# orangepi-util-40pin.net
KiCad netlist of a schematic drawn in EasyEDA Pro
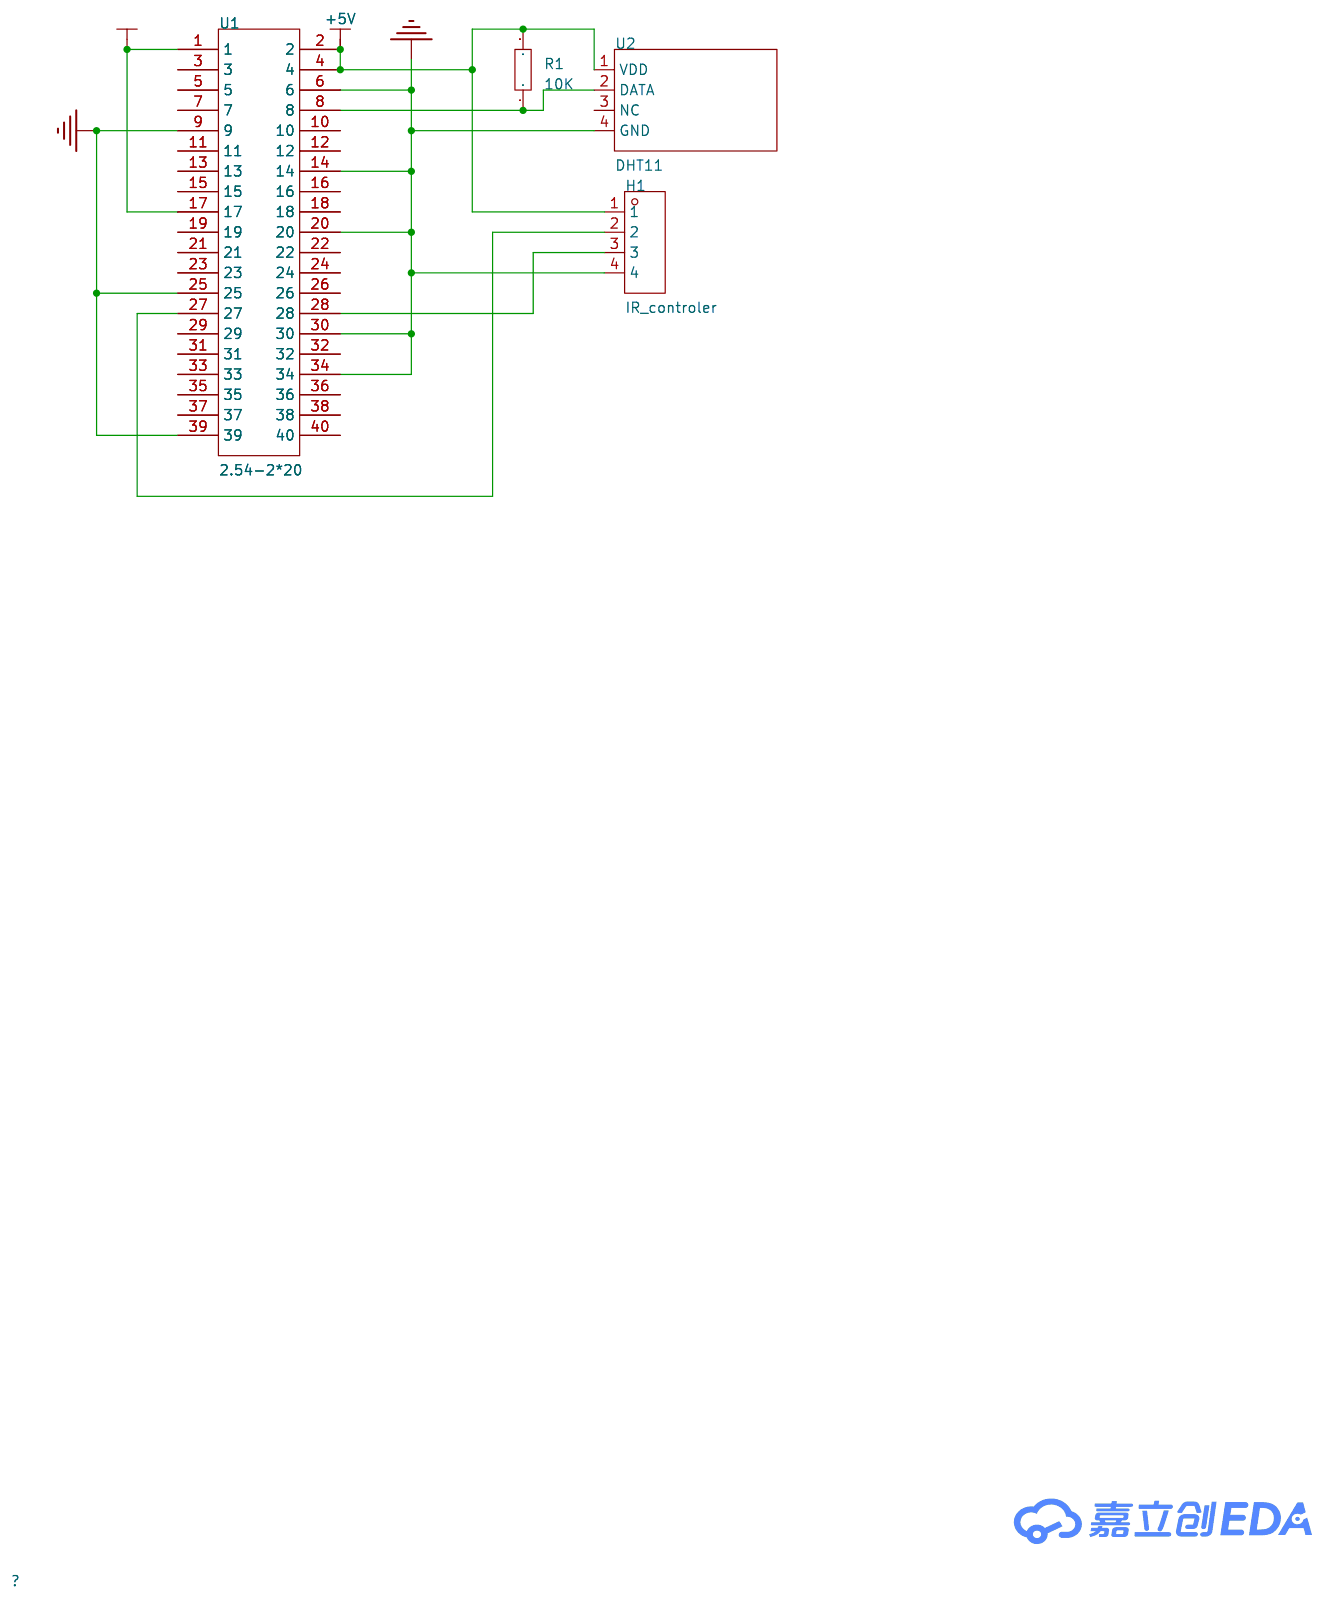
[diagram p0: schematic sheet]

(export (version "E")
  (design (tool "Eeschema 10.0.6"))
  (components
    (comp (ref "H1")
      (value "IR_controler")
      (footprint "easyedapro:HDR-TH_4P-P2.54-V-M")
      (fields (field (name "Manufacturer Part") "PZ254V-11-04P") (field (name "Manufacturer") "XFCN(兴飞)"))
      (libsource (lib "easyedapro") (part "PZ254V-11-04P_C2691448"))
    )
    (comp (ref "R1") (value "10K") (footprint "easyedapro:R0603") (libsource (lib "easyedapro") (part "电阻")))
    (comp (ref "U1")
      (value "2.54-2*20")
      (footprint "easyedapro:HDR-TH_40P-P2.54-V-F-R2-C20-S2.54")
      (fields (field (name "Manufacturer") "ZHOURI(洲日)"))
      (libsource (lib "easyedapro") (part "2.54-2*20"))
    )
    (comp (ref "U2")
      (value "DHT11")
      (footprint "easyedapro:SENSOR-TH_DHT11")
      (description "新款电容式数字温湿度传感器,老款已停产16.1x12.6x5.8mm")
      (fields (field (name "Manufacturer") "广州奥松"))
      (libsource (lib "easyedapro") (part "DHT11"))
    )
  )
  (nets
    (net (code "1") (name "+3.3V") (class "Default")
      (node (ref "U1") (pin "1") (pinfunction "1_1") (pintype "unspecified"))
      (node (ref "U1") (pin "17") (pinfunction "17_17") (pintype "unspecified"))
    )
    (net (code "2") (name "+5V") (class "Default")
      (node (ref "H1") (pin "1") (pinfunction "1_1") (pintype "unspecified"))
      (node (ref "R1") (pin "2") (pinfunction "2_2") (pintype "input"))
      (node (ref "U1") (pin "2") (pinfunction "2_2") (pintype "unspecified"))
      (node (ref "U1") (pin "4") (pinfunction "4_4") (pintype "unspecified"))
      (node (ref "U2") (pin "1") (pinfunction "VDD_1") (pintype "unspecified"))
    )
    (net (code "3") (name "GND") (class "Default")
      (node (ref "H1") (pin "4") (pinfunction "4_4") (pintype "unspecified"))
      (node (ref "U1") (pin "14") (pinfunction "14_14") (pintype "unspecified"))
      (node (ref "U1") (pin "20") (pinfunction "20_20") (pintype "unspecified"))
      (node (ref "U1") (pin "25") (pinfunction "25_25") (pintype "unspecified"))
      (node (ref "U1") (pin "30") (pinfunction "30_30") (pintype "unspecified"))
      (node (ref "U1") (pin "34") (pinfunction "34_34") (pintype "unspecified"))
      (node (ref "U1") (pin "39") (pinfunction "39_39") (pintype "unspecified"))
      (node (ref "U1") (pin "6") (pinfunction "6_6") (pintype "unspecified"))
      (node (ref "U1") (pin "9") (pinfunction "9_9") (pintype "unspecified"))
      (node (ref "U2") (pin "4") (pinfunction "GND_4") (pintype "unspecified"))
    )
    (net (code "4") (name "Net-(H1-Pad2)") (class "Default")
      (node (ref "H1") (pin "2") (pinfunction "2_2") (pintype "unspecified"))
      (node (ref "U1") (pin "27") (pinfunction "27_27") (pintype "unspecified"))
    )
    (net (code "5") (name "Net-(H1-Pad3)") (class "Default")
      (node (ref "H1") (pin "3") (pinfunction "3_3") (pintype "unspecified"))
      (node (ref "U1") (pin "28") (pinfunction "28_28") (pintype "unspecified"))
    )
    (net (code "6") (name "Net-(U2-DATA)") (class "Default")
      (node (ref "R1") (pin "1") (pinfunction "1_1") (pintype "input"))
      (node (ref "U1") (pin "8") (pinfunction "8_8") (pintype "unspecified"))
      (node (ref "U2") (pin "2") (pinfunction "DATA_2") (pintype "unspecified"))
    )
    (net (code "7") (name "unconnected-(U1-Pad3)") (class "Default")
      (node (ref "U1") (pin "3") (pinfunction "3_3") (pintype "unspecified"))
    )
    (net (code "8") (name "unconnected-(U1-Pad5)") (class "Default")
      (node (ref "U1") (pin "5") (pinfunction "5_5") (pintype "unspecified"))
    )
    (net (code "9") (name "unconnected-(U1-Pad7)") (class "Default")
      (node (ref "U1") (pin "7") (pinfunction "7_7") (pintype "unspecified"))
    )
    (net (code "10") (name "unconnected-(U1-Pad10)") (class "Default")
      (node (ref "U1") (pin "10") (pinfunction "10_10") (pintype "unspecified"))
    )
    (net (code "11") (name "unconnected-(U1-Pad11)") (class "Default")
      (node (ref "U1") (pin "11") (pinfunction "11_11") (pintype "unspecified"))
    )
    (net (code "12") (name "unconnected-(U1-Pad12)") (class "Default")
      (node (ref "U1") (pin "12") (pinfunction "12_12") (pintype "unspecified"))
    )
    (net (code "13") (name "unconnected-(U1-Pad13)") (class "Default")
      (node (ref "U1") (pin "13") (pinfunction "13_13") (pintype "unspecified"))
    )
    (net (code "14") (name "unconnected-(U1-Pad15)") (class "Default")
      (node (ref "U1") (pin "15") (pinfunction "15_15") (pintype "unspecified"))
    )
    (net (code "15") (name "unconnected-(U1-Pad16)") (class "Default")
      (node (ref "U1") (pin "16") (pinfunction "16_16") (pintype "unspecified"))
    )
    (net (code "16") (name "unconnected-(U1-Pad18)") (class "Default")
      (node (ref "U1") (pin "18") (pinfunction "18_18") (pintype "unspecified"))
    )
    (net (code "17") (name "unconnected-(U1-Pad19)") (class "Default")
      (node (ref "U1") (pin "19") (pinfunction "19_19") (pintype "unspecified"))
    )
    (net (code "18") (name "unconnected-(U1-Pad21)") (class "Default")
      (node (ref "U1") (pin "21") (pinfunction "21_21") (pintype "unspecified"))
    )
    (net (code "19") (name "unconnected-(U1-Pad22)") (class "Default")
      (node (ref "U1") (pin "22") (pinfunction "22_22") (pintype "unspecified"))
    )
    (net (code "20") (name "unconnected-(U1-Pad23)") (class "Default")
      (node (ref "U1") (pin "23") (pinfunction "23_23") (pintype "unspecified"))
    )
    (net (code "21") (name "unconnected-(U1-Pad24)") (class "Default")
      (node (ref "U1") (pin "24") (pinfunction "24_24") (pintype "unspecified"))
    )
    (net (code "22") (name "unconnected-(U1-Pad26)") (class "Default")
      (node (ref "U1") (pin "26") (pinfunction "26_26") (pintype "unspecified"))
    )
    (net (code "23") (name "unconnected-(U1-Pad29)") (class "Default")
      (node (ref "U1") (pin "29") (pinfunction "29_29") (pintype "unspecified"))
    )
    (net (code "24") (name "unconnected-(U1-Pad31)") (class "Default")
      (node (ref "U1") (pin "31") (pinfunction "31_31") (pintype "unspecified"))
    )
    (net (code "25") (name "unconnected-(U1-Pad32)") (class "Default")
      (node (ref "U1") (pin "32") (pinfunction "32_32") (pintype "unspecified"))
    )
    (net (code "26") (name "unconnected-(U1-Pad33)") (class "Default")
      (node (ref "U1") (pin "33") (pinfunction "33_33") (pintype "unspecified"))
    )
    (net (code "27") (name "unconnected-(U1-Pad35)") (class "Default")
      (node (ref "U1") (pin "35") (pinfunction "35_35") (pintype "unspecified"))
    )
    (net (code "28") (name "unconnected-(U1-Pad36)") (class "Default")
      (node (ref "U1") (pin "36") (pinfunction "36_36") (pintype "unspecified"))
    )
    (net (code "29") (name "unconnected-(U1-Pad37)") (class "Default")
      (node (ref "U1") (pin "37") (pinfunction "37_37") (pintype "unspecified"))
    )
    (net (code "30") (name "unconnected-(U1-Pad38)") (class "Default")
      (node (ref "U1") (pin "38") (pinfunction "38_38") (pintype "unspecified"))
    )
    (net (code "31") (name "unconnected-(U1-Pad40)") (class "Default")
      (node (ref "U1") (pin "40") (pinfunction "40_40") (pintype "unspecified"))
    )
    (net (code "32") (name "unconnected-(U2-NC-Pad3)") (class "Default")
      (node (ref "U2") (pin "3") (pinfunction "NC_3") (pintype "unspecified"))
    )
  )
)
